# PCB-TOP_FINAL.net
KiCad netlist of a schematic drawn in EAGLE
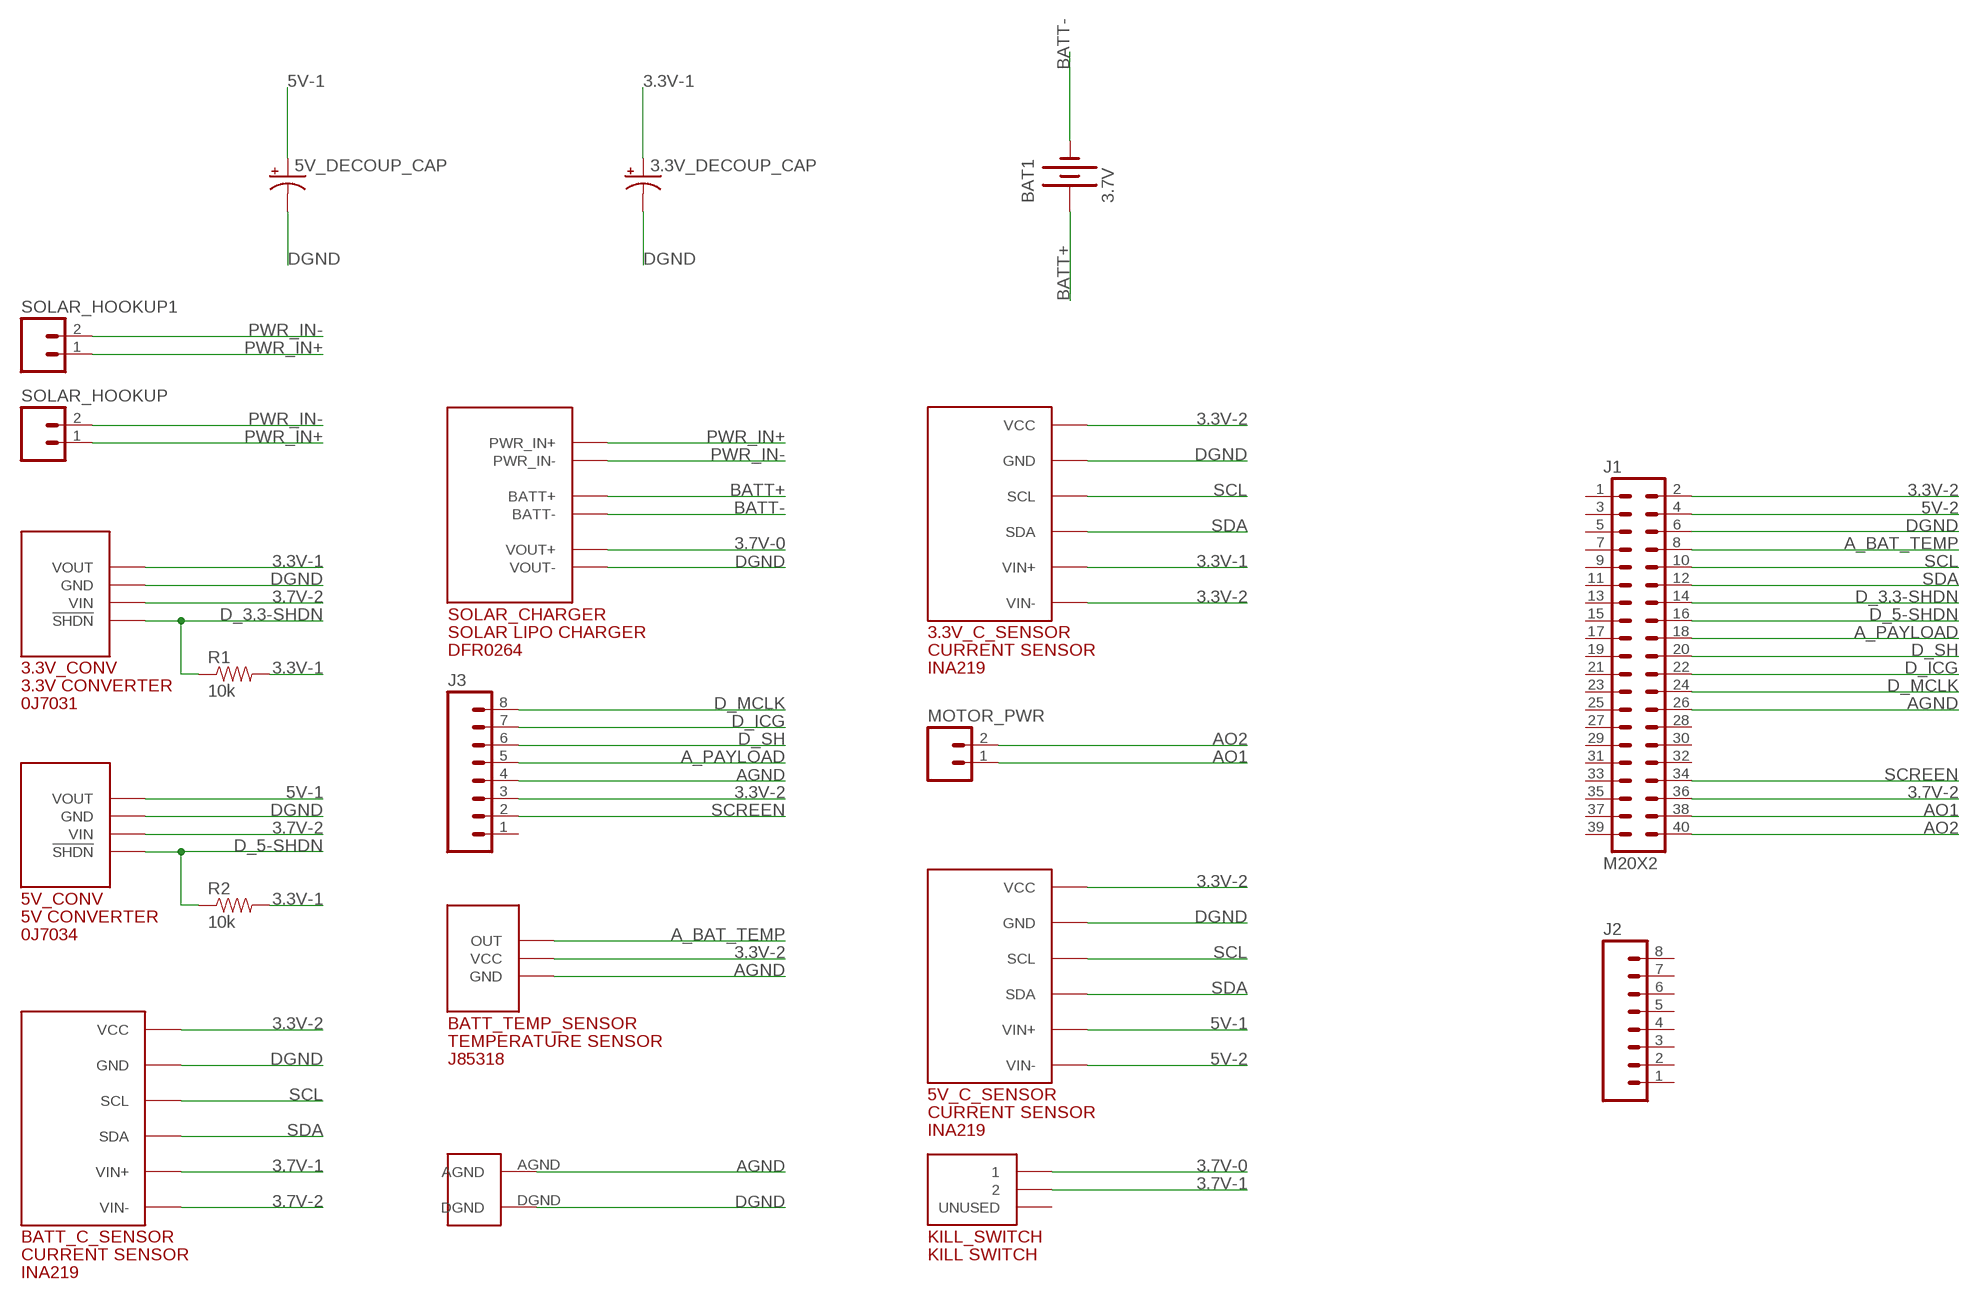
[diagram p0: schematic, sheet 1]

(export (version "E")
  (design (tool "Eeschema 10.0.6"))
  (components
    (comp (ref "3.3V_CONV")
      (value "3V3CONVERTERDIP4")
      (footprint "eagle-import:DIP4")
      (libsource (lib "eagle-import") (part "3V3CONVERTERDIP4"))
    )
    (comp (ref "3.3V_C_SENSOR")
      (value "ADAFRUIT_INA219_DEVICE")
      (footprint "eagle-import:C1_ADAFRUIT_INA219_CURPOWERMONITOR")
      (libsource (lib "eagle-import") (part "ADAFRUIT_INA219_DEVICE"))
    )
    (comp (ref "3.3V_DECOUP_CAP")
      (value "CAP_POLPTH1")
      (footprint "eagle-import:CPOL-RADIAL-100UF-25V")
      (libsource (lib "eagle-import") (part "CAP_POLPTH1"))
    )
    (comp (ref "5V_CONV")
      (value "DIP14DIP4")
      (footprint "eagle-import:DIP4")
      (libsource (lib "eagle-import") (part "DIP14DIP4"))
    )
    (comp (ref "5V_C_SENSOR")
      (value "ADAFRUIT_INA219_DEVICE")
      (footprint "eagle-import:C1_ADAFRUIT_INA219_CURPOWERMONITOR")
      (libsource (lib "eagle-import") (part "ADAFRUIT_INA219_DEVICE"))
    )
    (comp (ref "5V_DECOUP_CAP")
      (value "CAP_POLPTH1")
      (footprint "eagle-import:CPOL-RADIAL-100UF-25V")
      (libsource (lib "eagle-import") (part "CAP_POLPTH1"))
    )
    (comp (ref "BAT1")
      (value "3.7V")
      (footprint "eagle-import:BATTERY_18650-HOLDER")
      (libsource (lib "eagle-import") (part "BATTERY18650"))
    )
    (comp (ref "BATT_C_SENSOR")
      (value "ADAFRUIT_INA219_DEVICE")
      (footprint "eagle-import:C1_ADAFRUIT_INA219_CURPOWERMONITOR")
      (libsource (lib "eagle-import") (part "ADAFRUIT_INA219_DEVICE"))
    )
    (comp (ref "BATT_TEMP_SENSOR")
      (value "TEMP_SENSORDIP3")
      (footprint "eagle-import:DIP3")
      (libsource (lib "eagle-import") (part "TEMP_SENSORDIP3"))
    )
    (comp (ref "J1")
      (value "M20X2")
      (footprint "eagle-import:2X20")
      (libsource (lib "eagle-import") (part "M20X2"))
    )
    (comp (ref "J2")
      (value "M08")
      (footprint "eagle-import:1X08_ROUND")
      (libsource (lib "eagle-import") (part "M08"))
    )
    (comp (ref "J3")
      (value "M08")
      (footprint "eagle-import:1X08_ROUND")
      (libsource (lib "eagle-import") (part "M08"))
    )
    (comp (ref "KILL_SWITCH")
      (value "KILLSWITCH_V2_DEVICE")
      (footprint "eagle-import:KILLSWITCH_V2_PACKAGE")
      (libsource (lib "eagle-import") (part "KILLSWITCH_V2_DEVICE"))
    )
    (comp (ref "MOTOR_PWR")
      (value "M02PTH")
      (footprint "eagle-import:1X02")
      (libsource (lib "eagle-import") (part "M02PTH"))
    )
    (comp (ref "R1")
      (value "10k")
      (footprint "eagle-import:AXIAL-0.3")
      (libsource (lib "eagle-import") (part "10KOHM-1/4W-1%(PTH)HORIZ"))
    )
    (comp (ref "R2")
      (value "10k")
      (footprint "eagle-import:AXIAL-0.3")
      (libsource (lib "eagle-import") (part "10KOHM-1/4W-1%(PTH)HORIZ"))
    )
    (comp (ref "SOLAR_CHARGER")
      (value "SOLAR_CHARGER_DEVICE")
      (footprint "eagle-import:SOLAR_CHARGER_PACKAGE")
      (libsource (lib "eagle-import") (part "SOLAR_CHARGER_DEVICE"))
    )
    (comp (ref "SOLAR_HOOKUP")
      (value "M02PTH")
      (footprint "eagle-import:1X02")
      (libsource (lib "eagle-import") (part "M02PTH"))
    )
    (comp (ref "SOLAR_HOOKUP1")
      (value "M02PTH")
      (footprint "eagle-import:1X02")
      (libsource (lib "eagle-import") (part "M02PTH"))
    )
    (comp (ref "U$1")
      (value "GROUNDPLANECONNECTION_BOTTOM")
      (footprint "eagle-import:GROUNDPLANECONNECTION_BOTTOM")
      (libsource (lib "eagle-import") (part "GROUNDPLANECONNECTION_BOTTOM"))
    )
  )
  (nets
    (net (code "1") (name "/3.3V-1") (class "Default")
      (node (ref "3.3V_CONV") (pin "VOUT") (pinfunction "VOUT_VOUT") (pintype "bidirectional"))
      (node (ref "3.3V_C_SENSOR") (pin "VIN+") (pinfunction "VIN+_VIN+") (pintype "bidirectional"))
      (node (ref "3.3V_DECOUP_CAP") (pin "1") (pinfunction "+_1") (pintype "passive"))
      (node (ref "R1") (pin "P$2") (pinfunction "2_P$2") (pintype "passive"))
      (node (ref "R2") (pin "P$2") (pinfunction "2_P$2") (pintype "passive"))
    )
    (net (code "2") (name "/3.3V-2") (class "Default")
      (node (ref "3.3V_C_SENSOR") (pin "VCC") (pinfunction "VCC_VCC") (pintype "bidirectional"))
      (node (ref "3.3V_C_SENSOR") (pin "VIN-") (pinfunction "VIN-_VIN-") (pintype "bidirectional"))
      (node (ref "5V_C_SENSOR") (pin "VCC") (pinfunction "VCC_VCC") (pintype "bidirectional"))
      (node (ref "BATT_C_SENSOR") (pin "VCC") (pinfunction "VCC_VCC") (pintype "bidirectional"))
      (node (ref "BATT_TEMP_SENSOR") (pin "VCC") (pinfunction "VCC_VCC") (pintype "bidirectional"))
      (node (ref "J1") (pin "2") (pinfunction "2_2") (pintype "passive"))
      (node (ref "J3") (pin "3") (pinfunction "3_3") (pintype "passive"))
    )
    (net (code "3") (name "/3.7V-0") (class "Default")
      (node (ref "KILL_SWITCH") (pin "1") (pinfunction "1_1") (pintype "bidirectional"))
      (node (ref "SOLAR_CHARGER") (pin "VOUT+") (pinfunction "VOUT+_VOUT+") (pintype "bidirectional"))
    )
    (net (code "4") (name "/3.7V-1") (class "Default")
      (node (ref "BATT_C_SENSOR") (pin "VIN+") (pinfunction "VIN+_VIN+") (pintype "bidirectional"))
      (node (ref "KILL_SWITCH") (pin "2") (pinfunction "2_2") (pintype "bidirectional"))
    )
    (net (code "5") (name "/3.7V-2") (class "Default")
      (node (ref "3.3V_CONV") (pin "VIN") (pinfunction "VIN_VIN") (pintype "bidirectional"))
      (node (ref "5V_CONV") (pin "VIN") (pinfunction "VIN_VIN") (pintype "bidirectional"))
      (node (ref "BATT_C_SENSOR") (pin "VIN-") (pinfunction "VIN-_VIN-") (pintype "bidirectional"))
      (node (ref "J1") (pin "36") (pinfunction "36_36") (pintype "passive"))
    )
    (net (code "6") (name "/5V-1") (class "Default")
      (node (ref "5V_CONV") (pin "VOUT") (pinfunction "VOUT_VOUT") (pintype "bidirectional"))
      (node (ref "5V_C_SENSOR") (pin "VIN+") (pinfunction "VIN+_VIN+") (pintype "bidirectional"))
      (node (ref "5V_DECOUP_CAP") (pin "1") (pinfunction "+_1") (pintype "passive"))
    )
    (net (code "7") (name "/5V-2") (class "Default")
      (node (ref "5V_C_SENSOR") (pin "VIN-") (pinfunction "VIN-_VIN-") (pintype "bidirectional"))
      (node (ref "J1") (pin "4") (pinfunction "4_4") (pintype "passive"))
    )
    (net (code "8") (name "/AGND") (class "Default")
      (node (ref "BATT_TEMP_SENSOR") (pin "GND") (pinfunction "GND_GND") (pintype "bidirectional"))
      (node (ref "J1") (pin "26") (pinfunction "26_26") (pintype "passive"))
      (node (ref "J3") (pin "4") (pinfunction "4_4") (pintype "passive"))
      (node (ref "U$1") (pin "AGND") (pinfunction "AGND_AGND") (pintype "bidirectional"))
    )
    (net (code "9") (name "/AO1") (class "Default")
      (node (ref "J1") (pin "38") (pinfunction "38_38") (pintype "passive"))
      (node (ref "MOTOR_PWR") (pin "1") (pinfunction "1_1") (pintype "passive"))
    )
    (net (code "10") (name "/AO2") (class "Default")
      (node (ref "J1") (pin "40") (pinfunction "40_40") (pintype "passive"))
      (node (ref "MOTOR_PWR") (pin "2") (pinfunction "2_2") (pintype "passive"))
    )
    (net (code "11") (name "/A_BAT_TEMP") (class "Default")
      (node (ref "BATT_TEMP_SENSOR") (pin "OUT") (pinfunction "OUT_OUT") (pintype "bidirectional"))
      (node (ref "J1") (pin "8") (pinfunction "8_8") (pintype "passive"))
    )
    (net (code "12") (name "/A_PAYLOAD") (class "Default")
      (node (ref "J1") (pin "18") (pinfunction "18_18") (pintype "passive"))
      (node (ref "J3") (pin "5") (pinfunction "5_5") (pintype "passive"))
    )
    (net (code "13") (name "/BATT+") (class "Default")
      (node (ref "BAT1") (pin "PWR@1") (pinfunction "+_PWR@1") (pintype "power_in"))
      (node (ref "SOLAR_CHARGER") (pin "BATT+") (pinfunction "BATT+_BATT+") (pintype "bidirectional"))
    )
    (net (code "14") (name "/BATT-") (class "Default")
      (node (ref "BAT1") (pin "GND@1") (pinfunction "-_GND@1") (pintype "power_in"))
      (node (ref "SOLAR_CHARGER") (pin "BATT-") (pinfunction "BATT-_BATT-") (pintype "bidirectional"))
    )
    (net (code "15") (name "/DGND") (class "Default")
      (node (ref "3.3V_CONV") (pin "GND") (pinfunction "GND_GND") (pintype "bidirectional"))
      (node (ref "3.3V_C_SENSOR") (pin "GND") (pinfunction "GND_GND") (pintype "bidirectional"))
      (node (ref "3.3V_DECOUP_CAP") (pin "2") (pinfunction "-_2") (pintype "passive"))
      (node (ref "5V_CONV") (pin "GND") (pinfunction "GND_GND") (pintype "bidirectional"))
      (node (ref "5V_C_SENSOR") (pin "GND") (pinfunction "GND_GND") (pintype "bidirectional"))
      (node (ref "5V_DECOUP_CAP") (pin "2") (pinfunction "-_2") (pintype "passive"))
      (node (ref "BATT_C_SENSOR") (pin "GND") (pinfunction "GND_GND") (pintype "bidirectional"))
      (node (ref "J1") (pin "6") (pinfunction "6_6") (pintype "passive"))
      (node (ref "SOLAR_CHARGER") (pin "VOUT-") (pinfunction "VOUT-_VOUT-") (pintype "bidirectional"))
      (node (ref "U$1") (pin "DGND") (pinfunction "DGND_DGND") (pintype "bidirectional"))
    )
    (net (code "16") (name "/D_3.3-SHDN") (class "Default")
      (node (ref "3.3V_CONV") (pin "SHDN") (pinfunction "~{SHDN}_SHDN") (pintype "bidirectional"))
      (node (ref "J1") (pin "14") (pinfunction "14_14") (pintype "passive"))
      (node (ref "R1") (pin "P$1") (pinfunction "1_P$1") (pintype "passive"))
    )
    (net (code "17") (name "/D_5-SHDN") (class "Default")
      (node (ref "5V_CONV") (pin "SHDN") (pinfunction "~{SHDN}_SHDN") (pintype "bidirectional"))
      (node (ref "J1") (pin "16") (pinfunction "16_16") (pintype "passive"))
      (node (ref "R2") (pin "P$1") (pinfunction "1_P$1") (pintype "passive"))
    )
    (net (code "18") (name "/D_ICG") (class "Default")
      (node (ref "J1") (pin "22") (pinfunction "22_22") (pintype "passive"))
      (node (ref "J3") (pin "7") (pinfunction "7_7") (pintype "passive"))
    )
    (net (code "19") (name "/D_MCLK") (class "Default")
      (node (ref "J1") (pin "24") (pinfunction "24_24") (pintype "passive"))
      (node (ref "J3") (pin "8") (pinfunction "8_8") (pintype "passive"))
    )
    (net (code "20") (name "/D_SH") (class "Default")
      (node (ref "J1") (pin "20") (pinfunction "20_20") (pintype "passive"))
      (node (ref "J3") (pin "6") (pinfunction "6_6") (pintype "passive"))
    )
    (net (code "21") (name "/PWR_IN+") (class "Default")
      (node (ref "SOLAR_CHARGER") (pin "PWR_IN+") (pinfunction "PWR_IN+_PWR_IN+") (pintype "bidirectional"))
      (node (ref "SOLAR_HOOKUP") (pin "1") (pinfunction "1_1") (pintype "passive"))
      (node (ref "SOLAR_HOOKUP1") (pin "1") (pinfunction "1_1") (pintype "passive"))
    )
    (net (code "22") (name "/PWR_IN-") (class "Default")
      (node (ref "SOLAR_CHARGER") (pin "PWR_IN-") (pinfunction "PWR_IN-_PWR_IN-") (pintype "bidirectional"))
      (node (ref "SOLAR_HOOKUP") (pin "2") (pinfunction "2_2") (pintype "passive"))
      (node (ref "SOLAR_HOOKUP1") (pin "2") (pinfunction "2_2") (pintype "passive"))
    )
    (net (code "23") (name "/SCL") (class "Default")
      (node (ref "3.3V_C_SENSOR") (pin "SCL") (pinfunction "SCL_SCL") (pintype "bidirectional"))
      (node (ref "5V_C_SENSOR") (pin "SCL") (pinfunction "SCL_SCL") (pintype "bidirectional"))
      (node (ref "BATT_C_SENSOR") (pin "SCL") (pinfunction "SCL_SCL") (pintype "bidirectional"))
      (node (ref "J1") (pin "10") (pinfunction "10_10") (pintype "passive"))
    )
    (net (code "24") (name "/SCREEN") (class "Default")
      (node (ref "J1") (pin "34") (pinfunction "34_34") (pintype "passive"))
      (node (ref "J3") (pin "2") (pinfunction "2_2") (pintype "passive"))
    )
    (net (code "25") (name "/SDA") (class "Default")
      (node (ref "3.3V_C_SENSOR") (pin "SDA") (pinfunction "SDA_SDA") (pintype "bidirectional"))
      (node (ref "5V_C_SENSOR") (pin "SDA") (pinfunction "SDA_SDA") (pintype "bidirectional"))
      (node (ref "BATT_C_SENSOR") (pin "SDA") (pinfunction "SDA_SDA") (pintype "bidirectional"))
      (node (ref "J1") (pin "12") (pinfunction "12_12") (pintype "passive"))
    )
    (net (code "26") (name "unconnected-(J1-Pad1)") (class "Default")
      (node (ref "J1") (pin "1") (pinfunction "1_1") (pintype "passive"))
    )
    (net (code "27") (name "unconnected-(J1-Pad3)") (class "Default")
      (node (ref "J1") (pin "3") (pinfunction "3_3") (pintype "passive"))
    )
    (net (code "28") (name "unconnected-(J1-Pad5)") (class "Default")
      (node (ref "J1") (pin "5") (pinfunction "5_5") (pintype "passive"))
    )
    (net (code "29") (name "unconnected-(J1-Pad7)") (class "Default")
      (node (ref "J1") (pin "7") (pinfunction "7_7") (pintype "passive"))
    )
    (net (code "30") (name "unconnected-(J1-Pad9)") (class "Default")
      (node (ref "J1") (pin "9") (pinfunction "9_9") (pintype "passive"))
    )
    (net (code "31") (name "unconnected-(J1-Pad11)") (class "Default")
      (node (ref "J1") (pin "11") (pinfunction "11_11") (pintype "passive"))
    )
    (net (code "32") (name "unconnected-(J1-Pad13)") (class "Default")
      (node (ref "J1") (pin "13") (pinfunction "13_13") (pintype "passive"))
    )
    (net (code "33") (name "unconnected-(J1-Pad15)") (class "Default")
      (node (ref "J1") (pin "15") (pinfunction "15_15") (pintype "passive"))
    )
    (net (code "34") (name "unconnected-(J1-Pad17)") (class "Default")
      (node (ref "J1") (pin "17") (pinfunction "17_17") (pintype "passive"))
    )
    (net (code "35") (name "unconnected-(J1-Pad19)") (class "Default")
      (node (ref "J1") (pin "19") (pinfunction "19_19") (pintype "passive"))
    )
    (net (code "36") (name "unconnected-(J1-Pad21)") (class "Default")
      (node (ref "J1") (pin "21") (pinfunction "21_21") (pintype "passive"))
    )
    (net (code "37") (name "unconnected-(J1-Pad23)") (class "Default")
      (node (ref "J1") (pin "23") (pinfunction "23_23") (pintype "passive"))
    )
    (net (code "38") (name "unconnected-(J1-Pad25)") (class "Default")
      (node (ref "J1") (pin "25") (pinfunction "25_25") (pintype "passive"))
    )
    (net (code "39") (name "unconnected-(J1-Pad27)") (class "Default")
      (node (ref "J1") (pin "27") (pinfunction "27_27") (pintype "passive"))
    )
    (net (code "40") (name "unconnected-(J1-Pad28)") (class "Default")
      (node (ref "J1") (pin "28") (pinfunction "28_28") (pintype "passive"))
    )
    (net (code "41") (name "unconnected-(J1-Pad29)") (class "Default")
      (node (ref "J1") (pin "29") (pinfunction "29_29") (pintype "passive"))
    )
    (net (code "42") (name "unconnected-(J1-Pad30)") (class "Default")
      (node (ref "J1") (pin "30") (pinfunction "30_30") (pintype "passive"))
    )
    (net (code "43") (name "unconnected-(J1-Pad31)") (class "Default")
      (node (ref "J1") (pin "31") (pinfunction "31_31") (pintype "passive"))
    )
    (net (code "44") (name "unconnected-(J1-Pad32)") (class "Default")
      (node (ref "J1") (pin "32") (pinfunction "32_32") (pintype "passive"))
    )
    (net (code "45") (name "unconnected-(J1-Pad33)") (class "Default")
      (node (ref "J1") (pin "33") (pinfunction "33_33") (pintype "passive"))
    )
    (net (code "46") (name "unconnected-(J1-Pad35)") (class "Default")
      (node (ref "J1") (pin "35") (pinfunction "35_35") (pintype "passive"))
    )
    (net (code "47") (name "unconnected-(J1-Pad37)") (class "Default")
      (node (ref "J1") (pin "37") (pinfunction "37_37") (pintype "passive"))
    )
    (net (code "48") (name "unconnected-(J1-Pad39)") (class "Default")
      (node (ref "J1") (pin "39") (pinfunction "39_39") (pintype "passive"))
    )
    (net (code "49") (name "unconnected-(J2-Pad1)") (class "Default")
      (node (ref "J2") (pin "1") (pinfunction "1_1") (pintype "passive"))
    )
    (net (code "50") (name "unconnected-(J2-Pad2)") (class "Default")
      (node (ref "J2") (pin "2") (pinfunction "2_2") (pintype "passive"))
    )
    (net (code "51") (name "unconnected-(J2-Pad3)") (class "Default")
      (node (ref "J2") (pin "3") (pinfunction "3_3") (pintype "passive"))
    )
    (net (code "52") (name "unconnected-(J2-Pad4)") (class "Default")
      (node (ref "J2") (pin "4") (pinfunction "4_4") (pintype "passive"))
    )
    (net (code "53") (name "unconnected-(J2-Pad5)") (class "Default")
      (node (ref "J2") (pin "5") (pinfunction "5_5") (pintype "passive"))
    )
    (net (code "54") (name "unconnected-(J2-Pad6)") (class "Default")
      (node (ref "J2") (pin "6") (pinfunction "6_6") (pintype "passive"))
    )
    (net (code "55") (name "unconnected-(J2-Pad7)") (class "Default")
      (node (ref "J2") (pin "7") (pinfunction "7_7") (pintype "passive"))
    )
    (net (code "56") (name "unconnected-(J2-Pad8)") (class "Default")
      (node (ref "J2") (pin "8") (pinfunction "8_8") (pintype "passive"))
    )
    (net (code "57") (name "unconnected-(J3-Pad1)") (class "Default")
      (node (ref "J3") (pin "1") (pinfunction "1_1") (pintype "passive"))
    )
    (net (code "58") (name "unconnected-(KILL_SWITCH-PadUNUSED)") (class "Default")
      (node (ref "KILL_SWITCH") (pin "UNUSED") (pinfunction "UNUSED_UNUSED") (pintype "bidirectional"))
    )
  )
)
